# schematic_1.net
KiCad netlist of a schematic drawn in EAGLE
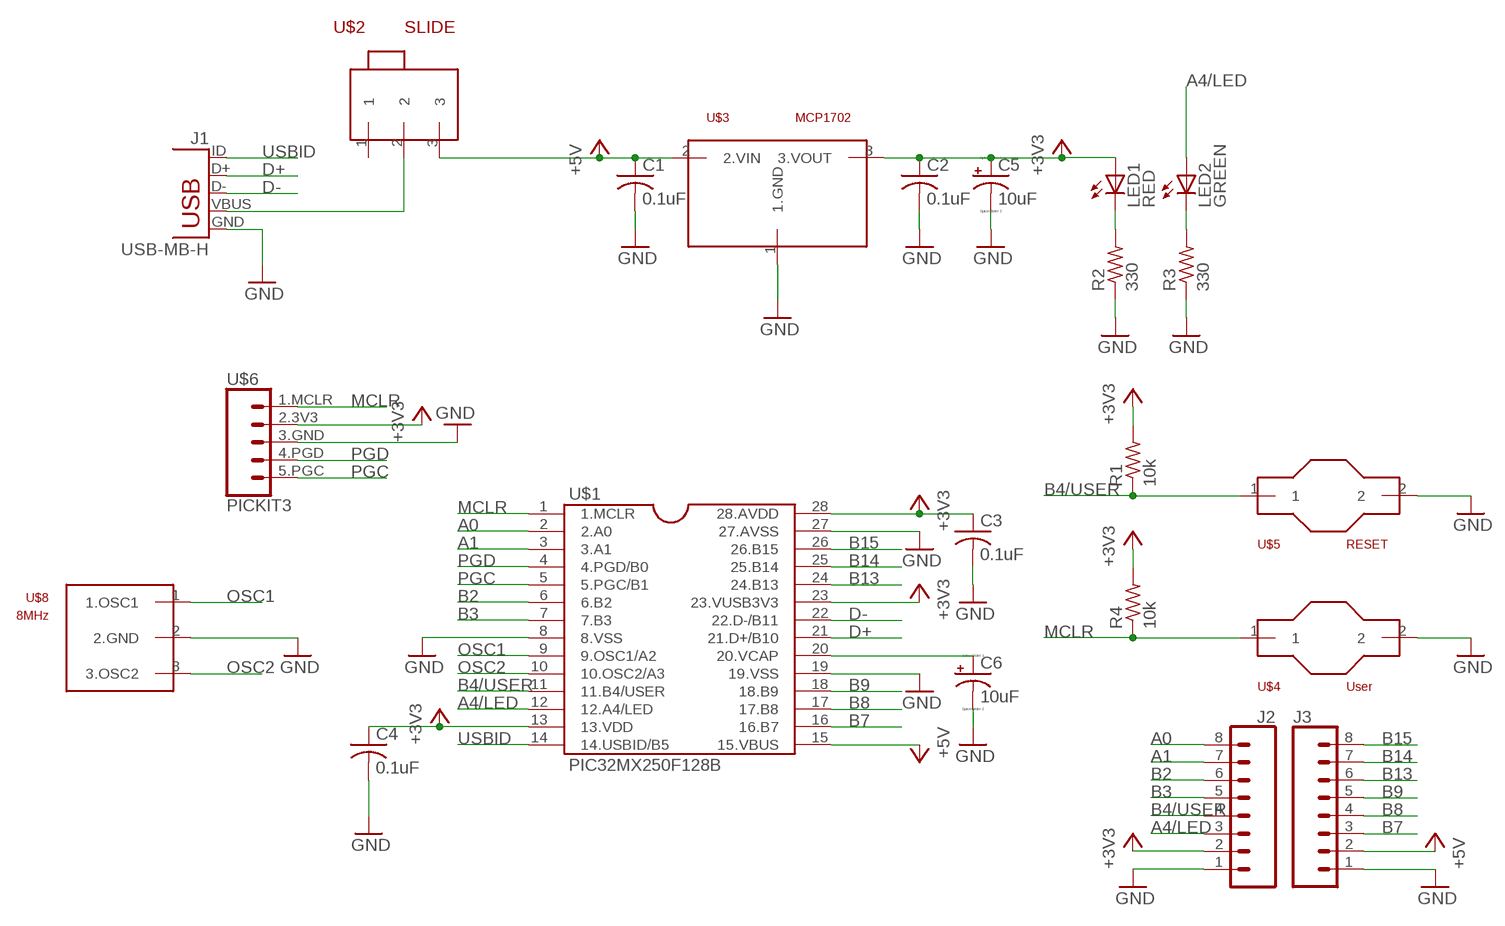
[diagram p0: schematic, sheet 1]

(export (version "E")
  (design (tool "Eeschema 10.0.6"))
  (components
    (comp (ref "C1")
      (value "0.1uF")
      (footprint "eagle-import:C025-025X050")
      (libsource (lib "eagle-import") (part "C-US025-025X050"))
    )
    (comp (ref "C2")
      (value "0.1uF")
      (footprint "eagle-import:C025-025X050")
      (libsource (lib "eagle-import") (part "C-US025-025X050"))
    )
    (comp (ref "C3")
      (value "0.1uF")
      (footprint "eagle-import:C025-025X050")
      (libsource (lib "eagle-import") (part "C-US025-025X050"))
    )
    (comp (ref "C4")
      (value "0.1uF")
      (footprint "eagle-import:C025-025X050")
      (libsource (lib "eagle-import") (part "C-US025-025X050"))
    )
    (comp (ref "C5")
      (value "10uF")
      (footprint "eagle-import:B45181B")
      (libsource (lib "eagle-import") (part "CPOL-USB45181B"))
    )
    (comp (ref "C6")
      (value "10uF")
      (footprint "eagle-import:B45181B")
      (libsource (lib "eagle-import") (part "CPOL-USB45181B"))
    )
    (comp (ref "J1")
      (value "USB-MB-H")
      (footprint "eagle-import:USB-MB-H")
      (libsource (lib "eagle-import") (part "USB-MB-H"))
    )
    (comp (ref "J2")
      (value "CONN_08\"")
      (footprint "eagle-import:1X08")
      (libsource (lib "eagle-import") (part "CONN_08{dblquote}"))
    )
    (comp (ref "J3")
      (value "CONN_08\"")
      (footprint "eagle-import:1X08")
      (libsource (lib "eagle-import") (part "CONN_08{dblquote}"))
    )
    (comp (ref "LED1")
      (value "RED")
      (footprint "eagle-import:LED3MM")
      (libsource (lib "eagle-import") (part "LED3MM"))
    )
    (comp (ref "LED2")
      (value "GREEN")
      (footprint "eagle-import:LED3MM")
      (libsource (lib "eagle-import") (part "LED3MM"))
    )
    (comp (ref "R1")
      (value "10k")
      (footprint "eagle-import:0207_10")
      (libsource (lib "eagle-import") (part "R-US_0207/10"))
    )
    (comp (ref "R2")
      (value "330")
      (footprint "eagle-import:0207_10")
      (libsource (lib "eagle-import") (part "R-US_0207/10"))
    )
    (comp (ref "R3")
      (value "330")
      (footprint "eagle-import:0207_10")
      (libsource (lib "eagle-import") (part "R-US_0207/10"))
    )
    (comp (ref "R4")
      (value "10k")
      (footprint "eagle-import:0207_10")
      (libsource (lib "eagle-import") (part "R-US_0207/10"))
    )
    (comp (ref "U$1")
      (value "PIC32MX250F128B")
      (footprint "eagle-import:DIL28-3")
      (libsource (lib "eagle-import") (part "PIC32MX250F128B"))
    )
    (comp (ref "U$2")
      (value "SLIDE")
      (footprint "eagle-import:SLIDE")
      (libsource (lib "eagle-import") (part "SLIDE"))
    )
    (comp (ref "U$3")
      (value "MCP1702")
      (footprint "eagle-import:TO92")
      (libsource (lib "eagle-import") (part "MCP1702"))
    )
    (comp (ref "U$4")
      (value "User")
      (footprint "eagle-import:BUTTON")
      (libsource (lib "eagle-import") (part "BUTTON"))
    )
    (comp (ref "U$5")
      (value "RESET")
      (footprint "eagle-import:BUTTON")
      (libsource (lib "eagle-import") (part "BUTTON"))
    )
    (comp (ref "U$6")
      (value "PICKIT3")
      (footprint "eagle-import:PICKIT3")
      (libsource (lib "eagle-import") (part "PICKIT3"))
    )
    (comp (ref "U$8")
      (value "8MHz")
      (footprint "eagle-import:OSC")
      (libsource (lib "eagle-import") (part "OSC"))
    )
  )
  (nets
    (net (code "1") (name "+3V3") (class "Default")
      (node (ref "C2") (pin "1") (pinfunction "1_1") (pintype "passive"))
      (node (ref "C3") (pin "1") (pinfunction "1_1") (pintype "passive"))
      (node (ref "C4") (pin "1") (pinfunction "1_1") (pintype "passive"))
      (node (ref "C5") (pin "+") (pinfunction "+_+") (pintype "passive"))
      (node (ref "J2") (pin "2") (pinfunction "2_2") (pintype "passive"))
      (node (ref "LED1") (pin "A") (pinfunction "A_A") (pintype "passive"))
      (node (ref "R1") (pin "2") (pinfunction "2_2") (pintype "passive"))
      (node (ref "R4") (pin "2") (pinfunction "2_2") (pintype "passive"))
      (node (ref "U$1") (pin "13") (pinfunction "13.VDD_13") (pintype "bidirectional"))
      (node (ref "U$1") (pin "23") (pinfunction "23.VUSB3V3_23") (pintype "bidirectional"))
      (node (ref "U$1") (pin "28") (pinfunction "28.AVDD_28") (pintype "bidirectional"))
      (node (ref "U$3") (pin "3") (pinfunction "3.VOUT_3") (pintype "bidirectional"))
      (node (ref "U$6") (pin "2.3V3") (pinfunction "2.VDD_2.3V3") (pintype "passive"))
    )
    (net (code "2") (name "+5V") (class "Default")
      (node (ref "C1") (pin "1") (pinfunction "1_1") (pintype "passive"))
      (node (ref "J3") (pin "2") (pinfunction "2_2") (pintype "passive"))
      (node (ref "U$1") (pin "15") (pinfunction "15.VBUS_15") (pintype "bidirectional"))
      (node (ref "U$2") (pin "3") (pinfunction "3_3") (pintype "bidirectional"))
      (node (ref "U$3") (pin "2") (pinfunction "2.VIN_2") (pintype "bidirectional"))
    )
    (net (code "3") (name "/A0") (class "Default")
      (node (ref "J2") (pin "8") (pinfunction "8_8") (pintype "passive"))
      (node (ref "U$1") (pin "2") (pinfunction "2.A0_2") (pintype "bidirectional"))
    )
    (net (code "4") (name "/A1") (class "Default")
      (node (ref "J2") (pin "7") (pinfunction "7_7") (pintype "passive"))
      (node (ref "U$1") (pin "3") (pinfunction "3.A1_3") (pintype "bidirectional"))
    )
    (net (code "5") (name "/A4{slash}LED") (class "Default")
      (node (ref "J2") (pin "3") (pinfunction "3_3") (pintype "passive"))
      (node (ref "LED2") (pin "A") (pinfunction "A_A") (pintype "passive"))
      (node (ref "U$1") (pin "12") (pinfunction "12.A4/LED_12") (pintype "bidirectional"))
    )
    (net (code "6") (name "/B2") (class "Default")
      (node (ref "J2") (pin "6") (pinfunction "6_6") (pintype "passive"))
      (node (ref "U$1") (pin "6") (pinfunction "6.B2_6") (pintype "bidirectional"))
    )
    (net (code "7") (name "/B3") (class "Default")
      (node (ref "J2") (pin "5") (pinfunction "5_5") (pintype "passive"))
      (node (ref "U$1") (pin "7") (pinfunction "7.B3_7") (pintype "bidirectional"))
    )
    (net (code "8") (name "/B4{slash}USER") (class "Default")
      (node (ref "J2") (pin "4") (pinfunction "4_4") (pintype "passive"))
      (node (ref "R1") (pin "1") (pinfunction "1_1") (pintype "passive"))
      (node (ref "U$1") (pin "11") (pinfunction "11.B4/USER_11") (pintype "bidirectional"))
      (node (ref "U$5") (pin "1") (pinfunction "1_1") (pintype "bidirectional"))
    )
    (net (code "9") (name "/B7") (class "Default")
      (node (ref "J3") (pin "3") (pinfunction "3_3") (pintype "passive"))
      (node (ref "U$1") (pin "16") (pinfunction "16.B7_16") (pintype "bidirectional"))
    )
    (net (code "10") (name "/B8") (class "Default")
      (node (ref "J3") (pin "4") (pinfunction "4_4") (pintype "passive"))
      (node (ref "U$1") (pin "17") (pinfunction "17.B8_17") (pintype "bidirectional"))
    )
    (net (code "11") (name "/B9") (class "Default")
      (node (ref "J3") (pin "5") (pinfunction "5_5") (pintype "passive"))
      (node (ref "U$1") (pin "18") (pinfunction "18.B9_18") (pintype "bidirectional"))
    )
    (net (code "12") (name "/B13") (class "Default")
      (node (ref "J3") (pin "6") (pinfunction "6_6") (pintype "passive"))
      (node (ref "U$1") (pin "24") (pinfunction "24.B13_24") (pintype "bidirectional"))
    )
    (net (code "13") (name "/B14") (class "Default")
      (node (ref "J3") (pin "7") (pinfunction "7_7") (pintype "passive"))
      (node (ref "U$1") (pin "25") (pinfunction "25.B14_25") (pintype "bidirectional"))
    )
    (net (code "14") (name "/B15") (class "Default")
      (node (ref "J3") (pin "8") (pinfunction "8_8") (pintype "passive"))
      (node (ref "U$1") (pin "26") (pinfunction "26.B15_26") (pintype "bidirectional"))
    )
    (net (code "15") (name "/D+") (class "Default")
      (node (ref "J1") (pin "D+") (pinfunction "D+_D+") (pintype "bidirectional"))
      (node (ref "U$1") (pin "21") (pinfunction "21.D+/B10_21") (pintype "bidirectional"))
    )
    (net (code "16") (name "/D-") (class "Default")
      (node (ref "J1") (pin "D-") (pinfunction "D-_D-") (pintype "bidirectional"))
      (node (ref "U$1") (pin "22") (pinfunction "22.D-/B11_22") (pintype "bidirectional"))
    )
    (net (code "17") (name "/MCLR") (class "Default")
      (node (ref "R4") (pin "1") (pinfunction "1_1") (pintype "passive"))
      (node (ref "U$1") (pin "1") (pinfunction "1.MCLR_1") (pintype "bidirectional"))
      (node (ref "U$4") (pin "1") (pinfunction "1_1") (pintype "bidirectional"))
      (node (ref "U$6") (pin "1.MCLR") (pinfunction "1.MCLR_1.MCLR") (pintype "passive"))
    )
    (net (code "18") (name "/OSC1") (class "Default")
      (node (ref "U$1") (pin "9") (pinfunction "9.OSC1/A2_9") (pintype "bidirectional"))
      (node (ref "U$8") (pin "1") (pinfunction "1.OSC1_1") (pintype "bidirectional"))
    )
    (net (code "19") (name "/OSC2") (class "Default")
      (node (ref "U$1") (pin "10") (pinfunction "10.OSC2/A3_10") (pintype "bidirectional"))
      (node (ref "U$8") (pin "3") (pinfunction "3.OSC2_3") (pintype "bidirectional"))
    )
    (net (code "20") (name "/PGC") (class "Default")
      (node (ref "U$1") (pin "5") (pinfunction "5.PGC/B1_5") (pintype "bidirectional"))
      (node (ref "U$6") (pin "5.PGC") (pinfunction "5.PGC_5.PGC") (pintype "passive"))
    )
    (net (code "21") (name "/PGD") (class "Default")
      (node (ref "U$1") (pin "4") (pinfunction "4.PGD/B0_4") (pintype "bidirectional"))
      (node (ref "U$6") (pin "4.PGD") (pinfunction "4.PGD_4.PGD") (pintype "passive"))
    )
    (net (code "22") (name "/USBID") (class "Default")
      (node (ref "J1") (pin "ID") (pinfunction "ID_ID") (pintype "bidirectional"))
      (node (ref "U$1") (pin "14") (pinfunction "14.USBID/B5_14") (pintype "bidirectional"))
    )
    (net (code "23") (name "GND") (class "Default")
      (node (ref "C1") (pin "2") (pinfunction "2_2") (pintype "passive"))
      (node (ref "C2") (pin "2") (pinfunction "2_2") (pintype "passive"))
      (node (ref "C3") (pin "2") (pinfunction "2_2") (pintype "passive"))
      (node (ref "C4") (pin "2") (pinfunction "2_2") (pintype "passive"))
      (node (ref "C5") (pin "-") (pinfunction "-_-") (pintype "passive"))
      (node (ref "C6") (pin "-") (pinfunction "-_-") (pintype "passive"))
      (node (ref "J1") (pin "GND") (pinfunction "GND_GND") (pintype "bidirectional"))
      (node (ref "J2") (pin "1") (pinfunction "1_1") (pintype "passive"))
      (node (ref "J3") (pin "1") (pinfunction "1_1") (pintype "passive"))
      (node (ref "R2") (pin "1") (pinfunction "1_1") (pintype "passive"))
      (node (ref "R3") (pin "1") (pinfunction "1_1") (pintype "passive"))
      (node (ref "U$1") (pin "19") (pinfunction "19.VSS_19") (pintype "bidirectional"))
      (node (ref "U$1") (pin "27") (pinfunction "27.AVSS_27") (pintype "bidirectional"))
      (node (ref "U$1") (pin "8") (pinfunction "8.VSS_8") (pintype "bidirectional"))
      (node (ref "U$3") (pin "1") (pinfunction "1.GND_1") (pintype "bidirectional"))
      (node (ref "U$4") (pin "2") (pinfunction "2_2") (pintype "bidirectional"))
      (node (ref "U$5") (pin "2") (pinfunction "2_2") (pintype "bidirectional"))
      (node (ref "U$6") (pin "3.GND") (pinfunction "3.GND_3.GND") (pintype "passive"))
      (node (ref "U$8") (pin "2") (pinfunction "2.GND_2") (pintype "bidirectional"))
    )
    (net (code "24") (name "Net-(J1-PadVBUS)") (class "Default")
      (node (ref "J1") (pin "VBUS") (pinfunction "VBUS_VBUS") (pintype "bidirectional"))
      (node (ref "U$2") (pin "2") (pinfunction "2_2") (pintype "bidirectional"))
    )
    (net (code "25") (name "Net-(LED1-C)") (class "Default")
      (node (ref "LED1") (pin "K") (pinfunction "C_K") (pintype "passive"))
      (node (ref "R2") (pin "2") (pinfunction "2_2") (pintype "passive"))
    )
    (net (code "26") (name "Net-(LED2-C)") (class "Default")
      (node (ref "LED2") (pin "K") (pinfunction "C_K") (pintype "passive"))
      (node (ref "R3") (pin "2") (pinfunction "2_2") (pintype "passive"))
    )
    (net (code "27") (name "Net-(U$1-20.VCAP)") (class "Default")
      (node (ref "C6") (pin "+") (pinfunction "+_+") (pintype "passive"))
      (node (ref "U$1") (pin "20") (pinfunction "20.VCAP_20") (pintype "bidirectional"))
    )
    (net (code "28") (name "unconnected-(U$2-Pad1)") (class "Default")
      (node (ref "U$2") (pin "1") (pinfunction "1_1") (pintype "bidirectional"))
    )
  )
)
